# ConnectorInterface.net
KiCad netlist of a schematic drawn in Altium Designer
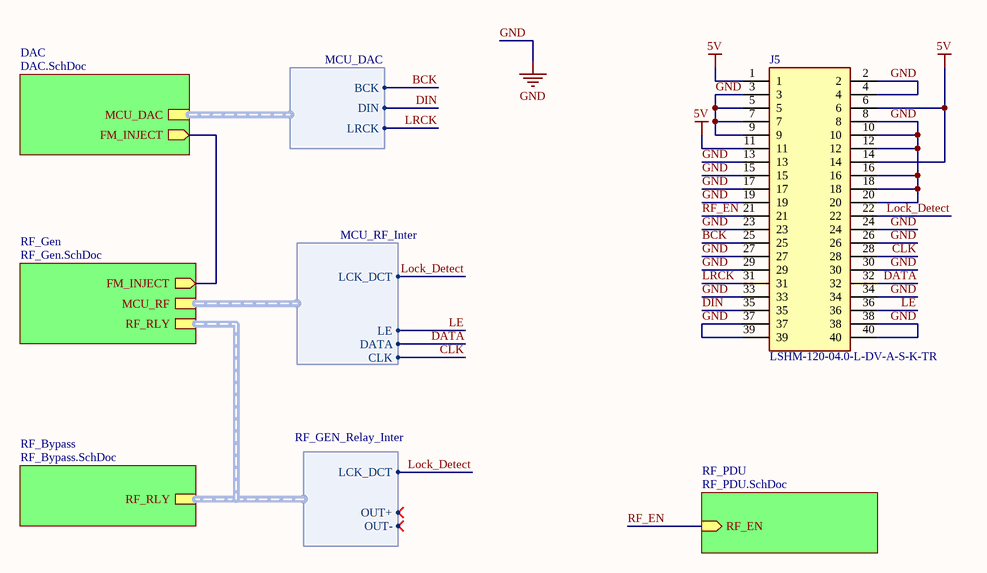
[diagram p0: ConnectorInterface.SchDoc]

(export (version "E")
  (design (tool "Eeschema 10.0.6"))
  (components
    (comp (ref "J5")
      (value "LSHM-120-04.0-L-DV-A-S-K-TR")
      (footprint "SamacSys:LSHM-120-XX.X-YYY-DV-A-S-K-TR")
      (description "Connector")
      (fields (field (name "MOUSER PART NUMBER") "200-LSHM12004LDVASK"))
      (libsource (lib "*") (part "LSHM-120-04.0-L-DV-A-S-K-TR"))
    )
  )
  (nets
    (net (code "4") (name "/BCK") (class "Default")
      (node (ref "J5") (pin "25") (pinfunction "25_25") (pintype "passive"))
    )
    (net (code "5") (name "/CLK") (class "Default")
      (node (ref "J5") (pin "28") (pinfunction "28_28") (pintype "passive"))
    )
    (net (code "6") (name "/DATA") (class "Default")
      (node (ref "J5") (pin "32") (pinfunction "32_32") (pintype "passive"))
    )
    (net (code "7") (name "/DIN") (class "Default")
      (node (ref "J5") (pin "35") (pinfunction "35_35") (pintype "passive"))
    )
    (net (code "9") (name "/LE") (class "Default")
      (node (ref "J5") (pin "36") (pinfunction "36_36") (pintype "passive"))
    )
    (net (code "10") (name "/LRCK") (class "Default")
      (node (ref "J5") (pin "31") (pinfunction "31_31") (pintype "passive"))
    )
    (net (code "11") (name "/Lock_Detect") (class "Default")
      (node (ref "J5") (pin "22") (pinfunction "22_22") (pintype "passive"))
    )
    (net (code "12") (name "/RF_EN") (class "Default")
      (node (ref "J5") (pin "21") (pinfunction "21_21") (pintype "passive"))
    )
    (net (code "16") (name "5V") (class "Default")
      (node (ref "J5") (pin "1") (pinfunction "1_1") (pintype "passive"))
      (node (ref "J5") (pin "11") (pinfunction "11_11") (pintype "passive"))
      (node (ref "J5") (pin "14") (pinfunction "14_14") (pintype "passive"))
      (node (ref "J5") (pin "6") (pinfunction "6_6") (pintype "passive"))
    )
    (net (code "17") (name "GND") (class "Default")
      (node (ref "J5") (pin "10") (pinfunction "10_10") (pintype "passive"))
      (node (ref "J5") (pin "12") (pinfunction "12_12") (pintype "passive"))
      (node (ref "J5") (pin "13") (pinfunction "13_13") (pintype "passive"))
      (node (ref "J5") (pin "15") (pinfunction "15_15") (pintype "passive"))
      (node (ref "J5") (pin "16") (pinfunction "16_16") (pintype "passive"))
      (node (ref "J5") (pin "17") (pinfunction "17_17") (pintype "passive"))
      (node (ref "J5") (pin "18") (pinfunction "18_18") (pintype "passive"))
      (node (ref "J5") (pin "19") (pinfunction "19_19") (pintype "passive"))
      (node (ref "J5") (pin "2") (pinfunction "2_2") (pintype "passive"))
      (node (ref "J5") (pin "20") (pinfunction "20_20") (pintype "passive"))
      (node (ref "J5") (pin "23") (pinfunction "23_23") (pintype "passive"))
      (node (ref "J5") (pin "24") (pinfunction "24_24") (pintype "passive"))
      (node (ref "J5") (pin "26") (pinfunction "26_26") (pintype "passive"))
      (node (ref "J5") (pin "27") (pinfunction "27_27") (pintype "passive"))
      (node (ref "J5") (pin "29") (pinfunction "29_29") (pintype "passive"))
      (node (ref "J5") (pin "3") (pinfunction "3_3") (pintype "passive"))
      (node (ref "J5") (pin "30") (pinfunction "30_30") (pintype "passive"))
      (node (ref "J5") (pin "33") (pinfunction "33_33") (pintype "passive"))
      (node (ref "J5") (pin "34") (pinfunction "34_34") (pintype "passive"))
      (node (ref "J5") (pin "37") (pinfunction "37_37") (pintype "passive"))
      (node (ref "J5") (pin "38") (pinfunction "38_38") (pintype "passive"))
      (node (ref "J5") (pin "39") (pinfunction "39_39") (pintype "passive"))
      (node (ref "J5") (pin "4") (pinfunction "4_4") (pintype "passive"))
      (node (ref "J5") (pin "40") (pinfunction "40_40") (pintype "passive"))
      (node (ref "J5") (pin "5") (pinfunction "5_5") (pintype "passive"))
      (node (ref "J5") (pin "7") (pinfunction "7_7") (pintype "passive"))
      (node (ref "J5") (pin "8") (pinfunction "8_8") (pintype "passive"))
      (node (ref "J5") (pin "9") (pinfunction "9_9") (pintype "passive"))
    )
  )
)
